# DCZia_MechKeyBadge.net
KiCad netlist of a schematic drawn in EAGLE
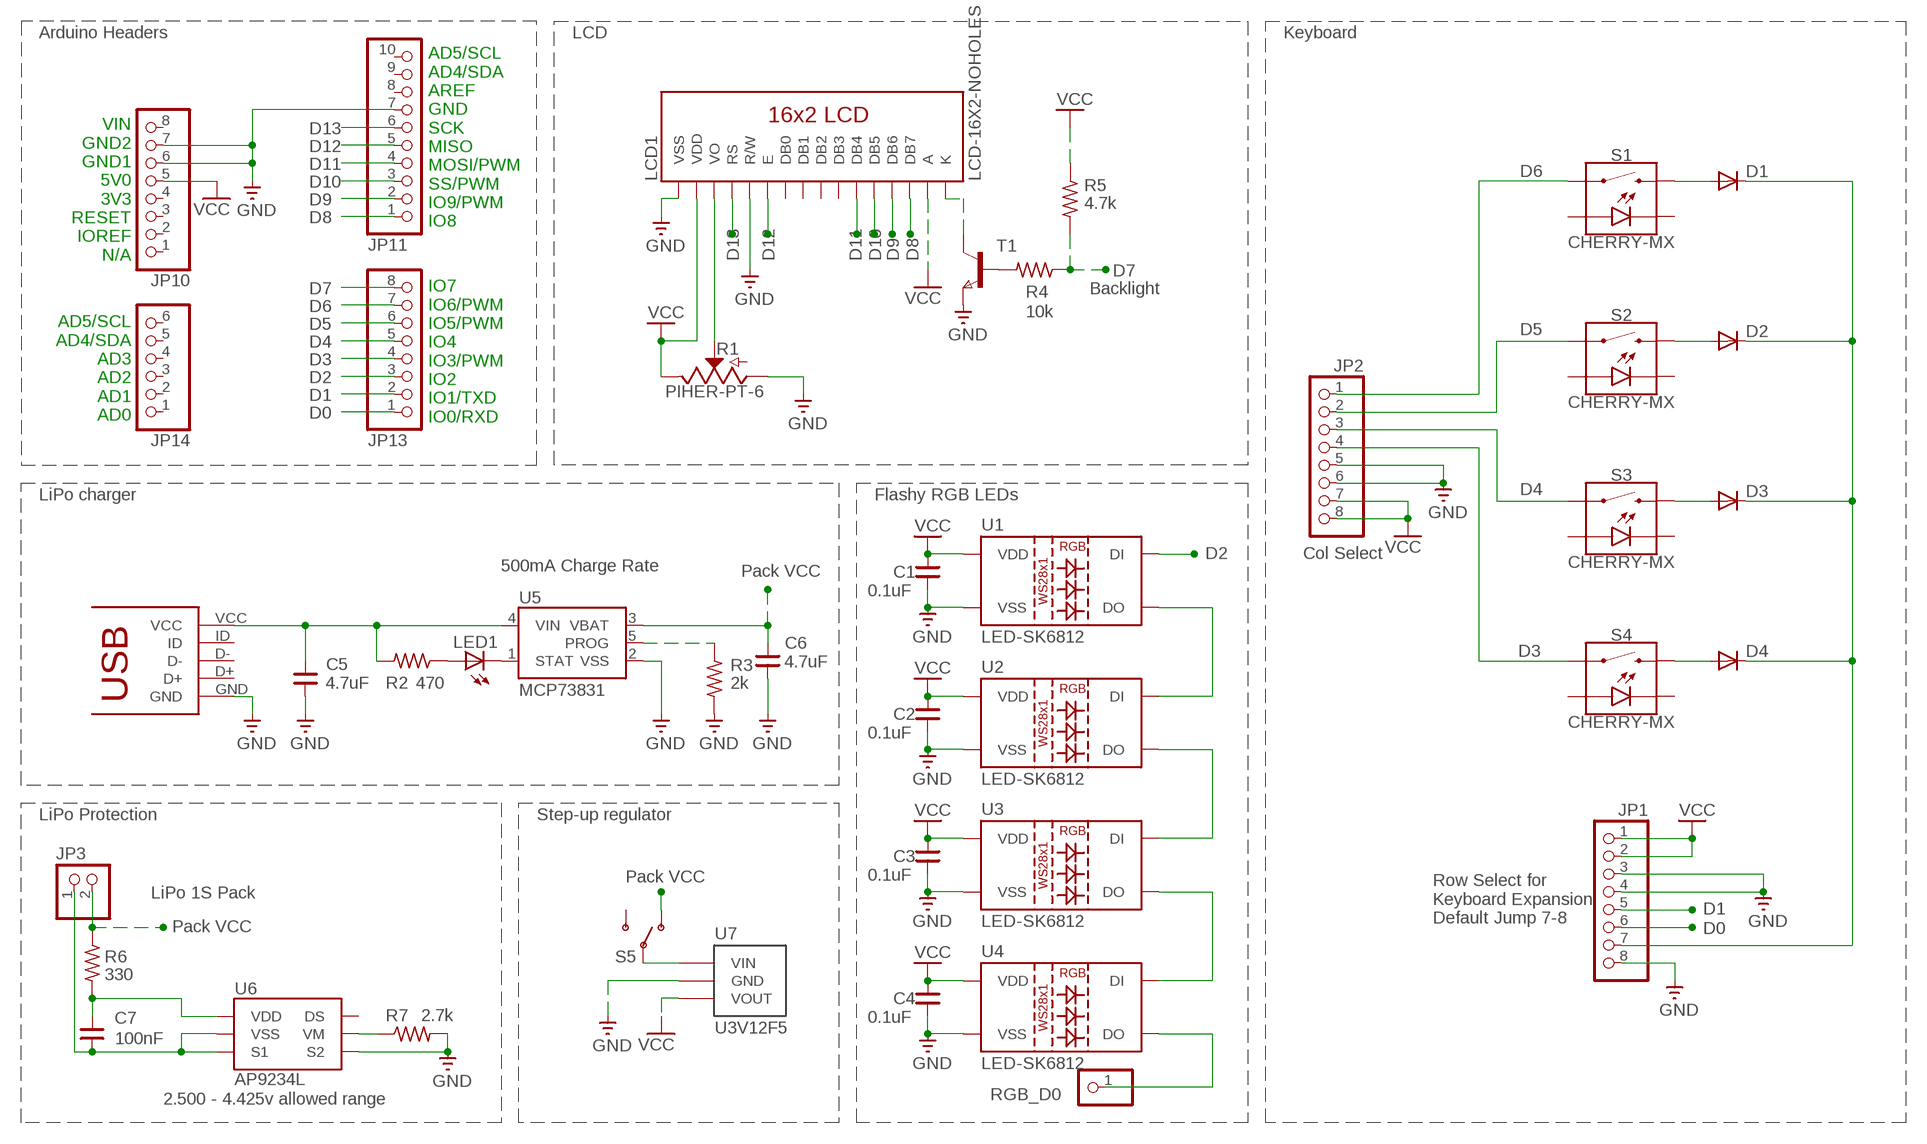
[diagram p0: schematic, sheet 1]

(export (version "E")
  (design (tool "Eeschema 10.0.6"))
  (components
    (comp (ref "C1")
      (value "0.1uF")
      (footprint "eagle-import:1206")
      (libsource (lib "eagle-import") (part "CNP-1206"))
    )
    (comp (ref "C2")
      (value "0.1uF")
      (footprint "eagle-import:1206")
      (libsource (lib "eagle-import") (part "CNP-1206"))
    )
    (comp (ref "C3")
      (value "0.1uF")
      (footprint "eagle-import:1206")
      (libsource (lib "eagle-import") (part "CNP-1206"))
    )
    (comp (ref "C4")
      (value "0.1uF")
      (footprint "eagle-import:1206")
      (libsource (lib "eagle-import") (part "CNP-1206"))
    )
    (comp (ref "C5")
      (value "4.7uF")
      (footprint "eagle-import:1206")
      (libsource (lib "eagle-import") (part "CNP-1206"))
    )
    (comp (ref "C6")
      (value "4.7uF")
      (footprint "eagle-import:1206")
      (libsource (lib "eagle-import") (part "CNP-1206"))
    )
    (comp (ref "C7")
      (value "100nF")
      (footprint "eagle-import:1206")
      (libsource (lib "eagle-import") (part "CNP-1206"))
    )
    (comp (ref "D1")
      (value "DIODE-SOD123")
      (footprint "eagle-import:SOD123")
      (libsource (lib "eagle-import") (part "DIODE-SOD123"))
    )
    (comp (ref "D2")
      (value "DIODE-SOD123")
      (footprint "eagle-import:SOD123")
      (libsource (lib "eagle-import") (part "DIODE-SOD123"))
    )
    (comp (ref "D3")
      (value "DIODE-SOD123")
      (footprint "eagle-import:SOD123")
      (libsource (lib "eagle-import") (part "DIODE-SOD123"))
    )
    (comp (ref "D4")
      (value "DIODE-SOD123")
      (footprint "eagle-import:SOD123")
      (libsource (lib "eagle-import") (part "DIODE-SOD123"))
    )
    (comp (ref "JP1")
      (value "PINHD-1X8")
      (footprint "eagle-import:1X08")
      (libsource (lib "eagle-import") (part "PINHD-1X8"))
    )
    (comp (ref "JP2")
      (value "PINHD-1X8")
      (footprint "eagle-import:1X08")
      (libsource (lib "eagle-import") (part "PINHD-1X8"))
    )
    (comp (ref "JP3")
      (value "PINHD-1X2")
      (footprint "eagle-import:1X02")
      (libsource (lib "eagle-import") (part "PINHD-1X2"))
    )
    (comp (ref "JP10")
      (value "PINHD-1X8")
      (footprint "eagle-import:1X08")
      (libsource (lib "eagle-import") (part "PINHD-1X8"))
    )
    (comp (ref "JP11")
      (value "PINHD-1X10")
      (footprint "eagle-import:1X10")
      (libsource (lib "eagle-import") (part "PINHD-1X10"))
    )
    (comp (ref "JP13")
      (value "PINHD-1X8")
      (footprint "eagle-import:1X08")
      (libsource (lib "eagle-import") (part "PINHD-1X8"))
    )
    (comp (ref "JP14")
      (value "PINHD-1X6")
      (footprint "eagle-import:1X06")
      (libsource (lib "eagle-import") (part "PINHD-1X6"))
    )
    (comp (ref "LCD1")
      (value "LCD-16X2-NOHOLES")
      (footprint "eagle-import:LCD-16X2")
      (libsource (lib "eagle-import") (part "LCD-16X2-NOHOLES"))
    )
    (comp (ref "LED1")
      (value "LEDSMT1206")
      (footprint "eagle-import:1206")
      (libsource (lib "eagle-import") (part "LEDSMT1206"))
    )
    (comp (ref "R1")
      (value "PIHER-PT-6")
      (footprint "eagle-import:PIHER-PT-6")
      (libsource (lib "eagle-import") (part "PIHER-PT-6"))
    )
    (comp (ref "R2")
      (value "470")
      (footprint "eagle-import:R1206")
      (libsource (lib "eagle-import") (part "R-US_R1206"))
    )
    (comp (ref "R3")
      (value "2k")
      (footprint "eagle-import:R1206")
      (libsource (lib "eagle-import") (part "R-US_R1206"))
    )
    (comp (ref "R4")
      (value "10k")
      (footprint "eagle-import:R1206")
      (libsource (lib "eagle-import") (part "R-US_R1206"))
    )
    (comp (ref "R5")
      (value "4.7k")
      (footprint "eagle-import:R1206")
      (libsource (lib "eagle-import") (part "R-US_R1206"))
    )
    (comp (ref "R6")
      (value "330")
      (footprint "eagle-import:R1206")
      (libsource (lib "eagle-import") (part "R-US_R1206"))
    )
    (comp (ref "R7")
      (value "2.7k")
      (footprint "eagle-import:R1206")
      (libsource (lib "eagle-import") (part "R-US_R1206"))
    )
    (comp (ref "RGB_D0")
      (value "PINHD-1X1")
      (footprint "eagle-import:1X01")
      (libsource (lib "eagle-import") (part "PINHD-1X1"))
    )
    (comp (ref "S1")
      (value "CHERRY-MX")
      (footprint "eagle-import:CHERRY-MX-LED")
      (libsource (lib "eagle-import") (part "CHERRY-MX"))
    )
    (comp (ref "S2")
      (value "CHERRY-MX")
      (footprint "eagle-import:CHERRY-MX-LED")
      (libsource (lib "eagle-import") (part "CHERRY-MX"))
    )
    (comp (ref "S3")
      (value "CHERRY-MX")
      (footprint "eagle-import:CHERRY-MX-LED")
      (libsource (lib "eagle-import") (part "CHERRY-MX"))
    )
    (comp (ref "S4")
      (value "CHERRY-MX")
      (footprint "eagle-import:CHERRY-MX-LED")
      (libsource (lib "eagle-import") (part "CHERRY-MX"))
    )
    (comp (ref "S5")
      (value "SWITCH-SPDTSMD")
      (footprint "eagle-import:SWITCH_SPDT_SMD")
      (libsource (lib "eagle-import") (part "SWITCH-SPDTSMD"))
    )
    (comp (ref "T1")
      (value "NPNSOT23")
      (footprint "eagle-import:SOT-23")
      (fields (field (name "MPN") "DSS20201L-7"))
      (libsource (lib "eagle-import") (part "NPNSOT23"))
    )
    (comp (ref "U$1")
      (value "10118192-0001LF")
      (footprint "eagle-import:10118192-0001LF")
      (libsource (lib "eagle-import") (part "10118192-0001LF"))
    )
    (comp (ref "U1")
      (value "LED-SK6812")
      (footprint "eagle-import:SK6812")
      (libsource (lib "eagle-import") (part "LED-SK6812"))
    )
    (comp (ref "U2")
      (value "LED-SK6812")
      (footprint "eagle-import:SK6812")
      (libsource (lib "eagle-import") (part "LED-SK6812"))
    )
    (comp (ref "U3")
      (value "LED-SK6812")
      (footprint "eagle-import:SK6812")
      (libsource (lib "eagle-import") (part "LED-SK6812"))
    )
    (comp (ref "U4")
      (value "LED-SK6812")
      (footprint "eagle-import:SK6812")
      (libsource (lib "eagle-import") (part "LED-SK6812"))
    )
    (comp (ref "U5")
      (value "MCP73831")
      (footprint "eagle-import:SOT23-5")
      (libsource (lib "eagle-import") (part "MCP73831"))
    )
    (comp (ref "U6")
      (value "AP9234L")
      (footprint "eagle-import:U-DFN2535-6")
      (libsource (lib "eagle-import") (part "AP9234L"))
    )
    (comp (ref "U7")
      (value "U3V12F5")
      (footprint "eagle-import:POLOLU_REGULATOR")
      (libsource (lib "eagle-import") (part "U3V12F5"))
    )
  )
  (nets
    (net (code "1") (name "/D0") (class "Default")
      (node (ref "JP1") (pin "6") (pinfunction "6_6") (pintype "passive"))
      (node (ref "JP13") (pin "1") (pinfunction "1_1") (pintype "passive"))
    )
    (net (code "2") (name "/D1") (class "Default")
      (node (ref "JP1") (pin "5") (pinfunction "5_5") (pintype "passive"))
      (node (ref "JP13") (pin "2") (pinfunction "2_2") (pintype "passive"))
    )
    (net (code "3") (name "/D2") (class "Default")
      (node (ref "JP13") (pin "3") (pinfunction "3_3") (pintype "passive"))
      (node (ref "U1") (pin "P$2") (pinfunction "DI_P$2") (pintype "bidirectional"))
    )
    (net (code "4") (name "/D3") (class "Default")
      (node (ref "JP13") (pin "4") (pinfunction "4_4") (pintype "passive"))
      (node (ref "JP2") (pin "4") (pinfunction "4_4") (pintype "passive"))
      (node (ref "S4") (pin "S1") (pinfunction "1_S1") (pintype "passive"))
    )
    (net (code "5") (name "/D4") (class "Default")
      (node (ref "JP13") (pin "5") (pinfunction "5_5") (pintype "passive"))
      (node (ref "JP2") (pin "3") (pinfunction "3_3") (pintype "passive"))
      (node (ref "S3") (pin "S1") (pinfunction "1_S1") (pintype "passive"))
    )
    (net (code "6") (name "/D5") (class "Default")
      (node (ref "JP13") (pin "6") (pinfunction "6_6") (pintype "passive"))
      (node (ref "JP2") (pin "2") (pinfunction "2_2") (pintype "passive"))
      (node (ref "S2") (pin "S1") (pinfunction "1_S1") (pintype "passive"))
    )
    (net (code "7") (name "/D6") (class "Default")
      (node (ref "JP13") (pin "7") (pinfunction "7_7") (pintype "passive"))
      (node (ref "JP2") (pin "1") (pinfunction "1_1") (pintype "passive"))
      (node (ref "S1") (pin "S1") (pinfunction "1_S1") (pintype "passive"))
    )
    (net (code "8") (name "/D7") (class "Default")
      (node (ref "JP13") (pin "8") (pinfunction "8_8") (pintype "passive"))
      (node (ref "R4") (pin "1") (pinfunction "1_1") (pintype "passive"))
      (node (ref "R5") (pin "2") (pinfunction "2_2") (pintype "passive"))
    )
    (net (code "9") (name "/D8") (class "Default")
      (node (ref "JP11") (pin "1") (pinfunction "1_1") (pintype "passive"))
      (node (ref "LCD1") (pin "14") (pinfunction "DB7_14") (pintype "bidirectional"))
    )
    (net (code "10") (name "/D9") (class "Default")
      (node (ref "JP11") (pin "2") (pinfunction "2_2") (pintype "passive"))
      (node (ref "LCD1") (pin "13") (pinfunction "DB6_13") (pintype "bidirectional"))
    )
    (net (code "11") (name "/D10") (class "Default")
      (node (ref "JP11") (pin "3") (pinfunction "3_3") (pintype "passive"))
      (node (ref "LCD1") (pin "12") (pinfunction "DB5_12") (pintype "bidirectional"))
    )
    (net (code "12") (name "/D11") (class "Default")
      (node (ref "JP11") (pin "4") (pinfunction "4_4") (pintype "passive"))
      (node (ref "LCD1") (pin "11") (pinfunction "DB4_11") (pintype "bidirectional"))
    )
    (net (code "13") (name "/D12") (class "Default")
      (node (ref "JP11") (pin "5") (pinfunction "5_5") (pintype "passive"))
      (node (ref "LCD1") (pin "6") (pinfunction "E_6") (pintype "input"))
    )
    (net (code "14") (name "/D13") (class "Default")
      (node (ref "JP11") (pin "6") (pinfunction "6_6") (pintype "passive"))
      (node (ref "LCD1") (pin "4") (pinfunction "RS_4") (pintype "input"))
    )
    (net (code "15") (name "/PACK_VCC") (class "Default")
      (node (ref "C6") (pin "P$2") (pinfunction "2_P$2") (pintype "passive"))
      (node (ref "JP3") (pin "2") (pinfunction "2_2") (pintype "passive"))
      (node (ref "R6") (pin "1") (pinfunction "1_1") (pintype "passive"))
      (node (ref "S5") (pin "1") (pinfunction "O_1") (pintype "passive"))
      (node (ref "U5") (pin "3") (pinfunction "VBAT_3") (pintype "power_in"))
    )
    (net (code "16") (name "GND") (class "Default")
      (node (ref "C1") (pin "P$1") (pinfunction "1_P$1") (pintype "passive"))
      (node (ref "C2") (pin "P$1") (pinfunction "1_P$1") (pintype "passive"))
      (node (ref "C3") (pin "P$1") (pinfunction "1_P$1") (pintype "passive"))
      (node (ref "C4") (pin "P$1") (pinfunction "1_P$1") (pintype "passive"))
      (node (ref "C5") (pin "P$1") (pinfunction "1_P$1") (pintype "passive"))
      (node (ref "C6") (pin "P$1") (pinfunction "1_P$1") (pintype "passive"))
      (node (ref "JP1") (pin "3") (pinfunction "3_3") (pintype "passive"))
      (node (ref "JP1") (pin "4") (pinfunction "4_4") (pintype "passive"))
      (node (ref "JP1") (pin "8") (pinfunction "8_8") (pintype "passive"))
      (node (ref "JP10") (pin "6") (pinfunction "6_6") (pintype "passive"))
      (node (ref "JP10") (pin "7") (pinfunction "7_7") (pintype "passive"))
      (node (ref "JP11") (pin "7") (pinfunction "7_7") (pintype "passive"))
      (node (ref "JP2") (pin "5") (pinfunction "5_5") (pintype "passive"))
      (node (ref "JP2") (pin "6") (pinfunction "6_6") (pintype "passive"))
      (node (ref "LCD1") (pin "1") (pinfunction "VSS_1") (pintype "power_in"))
      (node (ref "LCD1") (pin "5") (pinfunction "R/W_5") (pintype "input"))
      (node (ref "R1") (pin "P$1") (pinfunction "1_P$1") (pintype "passive"))
      (node (ref "R3") (pin "2") (pinfunction "2_2") (pintype "passive"))
      (node (ref "R7") (pin "2") (pinfunction "2_2") (pintype "passive"))
      (node (ref "T1") (pin "2") (pinfunction "E_2") (pintype "passive"))
      (node (ref "U$1") (pin "GND") (pinfunction "GND_GND") (pintype "bidirectional"))
      (node (ref "U1") (pin "P$1") (pinfunction "VSS_P$1") (pintype "bidirectional"))
      (node (ref "U2") (pin "P$1") (pinfunction "VSS_P$1") (pintype "bidirectional"))
      (node (ref "U3") (pin "P$1") (pinfunction "VSS_P$1") (pintype "bidirectional"))
      (node (ref "U4") (pin "P$1") (pinfunction "VSS_P$1") (pintype "bidirectional"))
      (node (ref "U5") (pin "2") (pinfunction "VSS_2") (pintype "power_in"))
      (node (ref "U6") (pin "S2") (pinfunction "S2_S2") (pintype "power_in"))
      (node (ref "U7") (pin "2") (pinfunction "GND_2") (pintype "power_in"))
    )
    (net (code "17") (name "Net-(C5-2)") (class "Default")
      (node (ref "C5") (pin "P$2") (pinfunction "2_P$2") (pintype "passive"))
      (node (ref "R2") (pin "2") (pinfunction "2_2") (pintype "passive"))
      (node (ref "U$1") (pin "VCC") (pinfunction "VCC_VCC") (pintype "bidirectional"))
      (node (ref "U5") (pin "4") (pinfunction "VIN_4") (pintype "power_in"))
    )
    (net (code "18") (name "Net-(C7-1)") (class "Default")
      (node (ref "C7") (pin "P$1") (pinfunction "1_P$1") (pintype "passive"))
      (node (ref "R6") (pin "2") (pinfunction "2_2") (pintype "passive"))
      (node (ref "U6") (pin "VDD") (pinfunction "VDD_VDD") (pintype "bidirectional"))
    )
    (net (code "19") (name "Net-(C7-2)") (class "Default")
      (node (ref "C7") (pin "P$2") (pinfunction "2_P$2") (pintype "passive"))
      (node (ref "JP3") (pin "1") (pinfunction "1_1") (pintype "passive"))
      (node (ref "U6") (pin "S1") (pinfunction "S1_S1") (pintype "power_in"))
      (node (ref "U6") (pin "VSS") (pinfunction "VSS_VSS") (pintype "power_in"))
    )
    (net (code "20") (name "Net-(D1-PadC)") (class "Default")
      (node (ref "D1") (pin "C") (pinfunction "C_C") (pintype "passive"))
      (node (ref "D2") (pin "C") (pinfunction "C_C") (pintype "passive"))
      (node (ref "D3") (pin "C") (pinfunction "C_C") (pintype "passive"))
      (node (ref "D4") (pin "C") (pinfunction "C_C") (pintype "passive"))
      (node (ref "JP1") (pin "7") (pinfunction "7_7") (pintype "passive"))
    )
    (net (code "21") (name "Net-(LCD1-K)") (class "Default")
      (node (ref "LCD1") (pin "16") (pinfunction "K_16") (pintype "power_in"))
      (node (ref "T1") (pin "1") (pinfunction "C_1") (pintype "passive"))
    )
    (net (code "22") (name "Net-(LCD1-VO)") (class "Default")
      (node (ref "LCD1") (pin "3") (pinfunction "VO_3") (pintype "bidirectional"))
      (node (ref "R1") (pin "P$2") (pinfunction "2_P$2") (pintype "passive"))
    )
    (net (code "23") (name "Net-(LED1-PadA)") (class "Default")
      (node (ref "LED1") (pin "A") (pinfunction "A_A") (pintype "passive"))
      (node (ref "R2") (pin "1") (pinfunction "1_1") (pintype "passive"))
    )
    (net (code "24") (name "Net-(R7-Pad1)") (class "Default")
      (node (ref "R7") (pin "1") (pinfunction "1_1") (pintype "passive"))
      (node (ref "U6") (pin "VM") (pinfunction "VM_VM") (pintype "bidirectional"))
    )
    (net (code "25") (name "Net-(S1-2)") (class "Default")
      (node (ref "D1") (pin "A") (pinfunction "A_A") (pintype "passive"))
      (node (ref "S1") (pin "S2") (pinfunction "2_S2") (pintype "passive"))
    )
    (net (code "26") (name "Net-(S2-2)") (class "Default")
      (node (ref "D2") (pin "A") (pinfunction "A_A") (pintype "passive"))
      (node (ref "S2") (pin "S2") (pinfunction "2_S2") (pintype "passive"))
    )
    (net (code "27") (name "Net-(S3-2)") (class "Default")
      (node (ref "D3") (pin "A") (pinfunction "A_A") (pintype "passive"))
      (node (ref "S3") (pin "S2") (pinfunction "2_S2") (pintype "passive"))
    )
    (net (code "28") (name "Net-(S4-2)") (class "Default")
      (node (ref "D4") (pin "A") (pinfunction "A_A") (pintype "passive"))
      (node (ref "S4") (pin "S2") (pinfunction "2_S2") (pintype "passive"))
    )
    (net (code "29") (name "Net-(S5-P)") (class "Default")
      (node (ref "S5") (pin "2") (pinfunction "P_2") (pintype "passive"))
      (node (ref "U7") (pin "3") (pinfunction "VIN_3") (pintype "power_in"))
    )
    (net (code "30") (name "Net-(T1-B)") (class "Default")
      (node (ref "R4") (pin "2") (pinfunction "2_2") (pintype "passive"))
      (node (ref "T1") (pin "3") (pinfunction "B_3") (pintype "passive"))
    )
    (net (code "31") (name "Net-(U1-DO)") (class "Default")
      (node (ref "U1") (pin "P$4") (pinfunction "DO_P$4") (pintype "bidirectional"))
      (node (ref "U2") (pin "P$2") (pinfunction "DI_P$2") (pintype "bidirectional"))
    )
    (net (code "32") (name "Net-(U2-DO)") (class "Default")
      (node (ref "U2") (pin "P$4") (pinfunction "DO_P$4") (pintype "bidirectional"))
      (node (ref "U3") (pin "P$2") (pinfunction "DI_P$2") (pintype "bidirectional"))
    )
    (net (code "33") (name "Net-(U3-DO)") (class "Default")
      (node (ref "U3") (pin "P$4") (pinfunction "DO_P$4") (pintype "bidirectional"))
      (node (ref "U4") (pin "P$2") (pinfunction "DI_P$2") (pintype "bidirectional"))
    )
    (net (code "34") (name "Net-(U4-DO)") (class "Default")
      (node (ref "RGB_D0") (pin "1") (pinfunction "1_1") (pintype "passive"))
      (node (ref "U4") (pin "P$4") (pinfunction "DO_P$4") (pintype "bidirectional"))
    )
    (net (code "35") (name "Net-(U5-PROG)") (class "Default")
      (node (ref "R3") (pin "1") (pinfunction "1_1") (pintype "passive"))
      (node (ref "U5") (pin "5") (pinfunction "PROG_5") (pintype "input"))
    )
    (net (code "36") (name "Net-(U5-STAT)") (class "Default")
      (node (ref "LED1") (pin "C") (pinfunction "C_C") (pintype "passive"))
      (node (ref "U5") (pin "1") (pinfunction "STAT_1") (pintype "output"))
    )
    (net (code "37") (name "VCC") (class "Default")
      (node (ref "C1") (pin "P$2") (pinfunction "2_P$2") (pintype "passive"))
      (node (ref "C2") (pin "P$2") (pinfunction "2_P$2") (pintype "passive"))
      (node (ref "C3") (pin "P$2") (pinfunction "2_P$2") (pintype "passive"))
      (node (ref "C4") (pin "P$2") (pinfunction "2_P$2") (pintype "passive"))
      (node (ref "JP1") (pin "1") (pinfunction "1_1") (pintype "passive"))
      (node (ref "JP1") (pin "2") (pinfunction "2_2") (pintype "passive"))
      (node (ref "JP10") (pin "5") (pinfunction "5_5") (pintype "passive"))
      (node (ref "JP2") (pin "7") (pinfunction "7_7") (pintype "passive"))
      (node (ref "JP2") (pin "8") (pinfunction "8_8") (pintype "passive"))
      (node (ref "LCD1") (pin "15") (pinfunction "A_15") (pintype "power_in"))
      (node (ref "LCD1") (pin "2") (pinfunction "VDD_2") (pintype "power_in"))
      (node (ref "R1") (pin "P$3") (pinfunction "3_P$3") (pintype "passive"))
      (node (ref "R5") (pin "1") (pinfunction "1_1") (pintype "passive"))
      (node (ref "U1") (pin "P$3") (pinfunction "VDD_P$3") (pintype "bidirectional"))
      (node (ref "U2") (pin "P$3") (pinfunction "VDD_P$3") (pintype "bidirectional"))
      (node (ref "U3") (pin "P$3") (pinfunction "VDD_P$3") (pintype "bidirectional"))
      (node (ref "U4") (pin "P$3") (pinfunction "VDD_P$3") (pintype "bidirectional"))
      (node (ref "U7") (pin "1") (pinfunction "VOUT_1") (pintype "bidirectional"))
    )
    (net (code "38") (name "unconnected-(JP10-Pad1)") (class "Default")
      (node (ref "JP10") (pin "1") (pinfunction "1_1") (pintype "passive"))
    )
    (net (code "39") (name "unconnected-(JP10-Pad2)") (class "Default")
      (node (ref "JP10") (pin "2") (pinfunction "2_2") (pintype "passive"))
    )
    (net (code "40") (name "unconnected-(JP10-Pad3)") (class "Default")
      (node (ref "JP10") (pin "3") (pinfunction "3_3") (pintype "passive"))
    )
    (net (code "41") (name "unconnected-(JP10-Pad4)") (class "Default")
      (node (ref "JP10") (pin "4") (pinfunction "4_4") (pintype "passive"))
    )
    (net (code "42") (name "unconnected-(JP10-Pad8)") (class "Default")
      (node (ref "JP10") (pin "8") (pinfunction "8_8") (pintype "passive"))
    )
    (net (code "43") (name "unconnected-(JP11-Pad8)") (class "Default")
      (node (ref "JP11") (pin "8") (pinfunction "8_8") (pintype "passive"))
    )
    (net (code "44") (name "unconnected-(JP11-Pad9)") (class "Default")
      (node (ref "JP11") (pin "9") (pinfunction "9_9") (pintype "passive"))
    )
    (net (code "45") (name "unconnected-(JP11-Pad10)") (class "Default")
      (node (ref "JP11") (pin "10") (pinfunction "10_10") (pintype "passive"))
    )
    (net (code "46") (name "unconnected-(JP14-Pad1)") (class "Default")
      (node (ref "JP14") (pin "1") (pinfunction "1_1") (pintype "passive"))
    )
    (net (code "47") (name "unconnected-(JP14-Pad2)") (class "Default")
      (node (ref "JP14") (pin "2") (pinfunction "2_2") (pintype "passive"))
    )
    (net (code "48") (name "unconnected-(JP14-Pad3)") (class "Default")
      (node (ref "JP14") (pin "3") (pinfunction "3_3") (pintype "passive"))
    )
    (net (code "49") (name "unconnected-(JP14-Pad4)") (class "Default")
      (node (ref "JP14") (pin "4") (pinfunction "4_4") (pintype "passive"))
    )
    (net (code "50") (name "unconnected-(JP14-Pad5)") (class "Default")
      (node (ref "JP14") (pin "5") (pinfunction "5_5") (pintype "passive"))
    )
    (net (code "51") (name "unconnected-(JP14-Pad6)") (class "Default")
      (node (ref "JP14") (pin "6") (pinfunction "6_6") (pintype "passive"))
    )
    (net (code "52") (name "unconnected-(LCD1-DB0-Pad7)") (class "Default")
      (node (ref "LCD1") (pin "7") (pinfunction "DB0_7") (pintype "bidirectional"))
    )
    (net (code "53") (name "unconnected-(LCD1-DB1-Pad8)") (class "Default")
      (node (ref "LCD1") (pin "8") (pinfunction "DB1_8") (pintype "bidirectional"))
    )
    (net (code "54") (name "unconnected-(LCD1-DB2-Pad9)") (class "Default")
      (node (ref "LCD1") (pin "9") (pinfunction "DB2_9") (pintype "bidirectional"))
    )
    (net (code "55") (name "unconnected-(LCD1-DB3-Pad10)") (class "Default")
      (node (ref "LCD1") (pin "10") (pinfunction "DB3_10") (pintype "bidirectional"))
    )
    (net (code "56") (name "unconnected-(S1-C-PadK)") (class "Default")
      (node (ref "S1") (pin "K") (pinfunction "C_K") (pintype "passive"))
    )
    (net (code "57") (name "unconnected-(S1-PadA)") (class "Default")
      (node (ref "S1") (pin "A") (pinfunction "A_A") (pintype "passive"))
    )
    (net (code "58") (name "unconnected-(S2-C-PadK)") (class "Default")
      (node (ref "S2") (pin "K") (pinfunction "C_K") (pintype "passive"))
    )
    (net (code "59") (name "unconnected-(S2-PadA)") (class "Default")
      (node (ref "S2") (pin "A") (pinfunction "A_A") (pintype "passive"))
    )
    (net (code "60") (name "unconnected-(S3-C-PadK)") (class "Default")
      (node (ref "S3") (pin "K") (pinfunction "C_K") (pintype "passive"))
    )
    (net (code "61") (name "unconnected-(S3-PadA)") (class "Default")
      (node (ref "S3") (pin "A") (pinfunction "A_A") (pintype "passive"))
    )
    (net (code "62") (name "unconnected-(S4-C-PadK)") (class "Default")
      (node (ref "S4") (pin "K") (pinfunction "C_K") (pintype "passive"))
    )
    (net (code "63") (name "unconnected-(S4-PadA)") (class "Default")
      (node (ref "S4") (pin "A") (pinfunction "A_A") (pintype "passive"))
    )
    (net (code "64") (name "unconnected-(S5-S-Pad3)") (class "Default")
      (node (ref "S5") (pin "3") (pinfunction "S_3") (pintype "passive"))
    )
    (net (code "65") (name "unconnected-(U$1-PadD+)") (class "Default")
      (node (ref "U$1") (pin "D+") (pinfunction "D+_D+") (pintype "bidirectional"))
    )
    (net (code "66") (name "unconnected-(U$1-PadD-)") (class "Default")
      (node (ref "U$1") (pin "D-") (pinfunction "D-_D-") (pintype "bidirectional"))
    )
    (net (code "67") (name "unconnected-(U$1-PadID)") (class "Default")
      (node (ref "U$1") (pin "ID") (pinfunction "ID_ID") (pintype "bidirectional"))
    )
    (net (code "68") (name "unconnected-(U6-PadDS)") (class "Default")
      (node (ref "U6") (pin "DS") (pinfunction "DS_DS") (pintype "bidirectional"))
    )
  )
)
